# Sony_remote.net
KiCad netlist of a schematic drawn in EAGLE
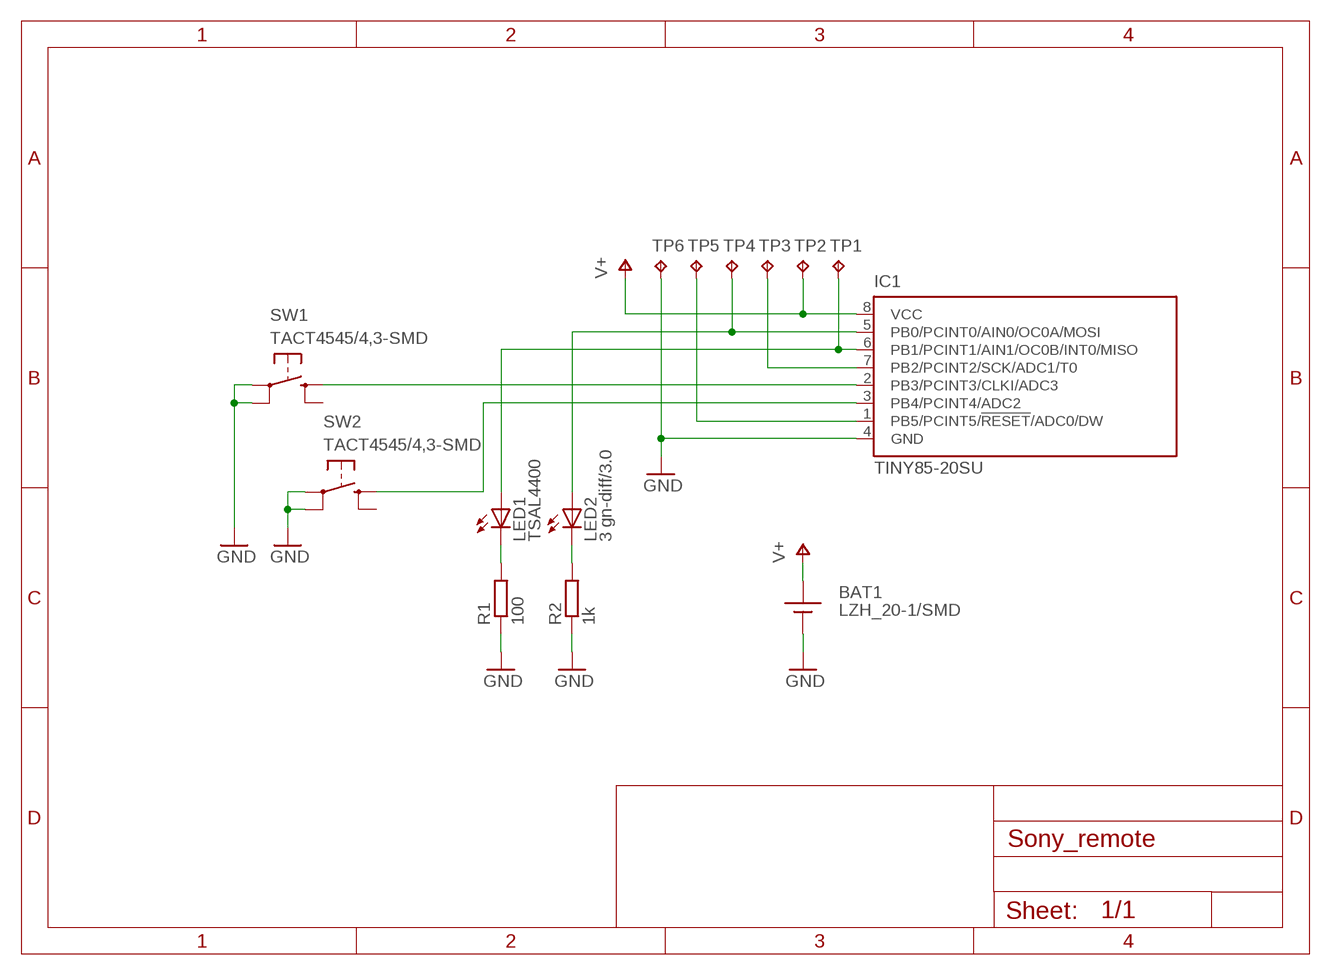
[diagram p0: schematic, sheet 1]

(export (version "E")
  (design (tool "Eeschema 10.0.6"))
  (components
    (comp (ref "BAT1")
      (value "LZH_20-1/SMD")
      (footprint "eagle-import:LZH_20-1_SMD")
      (libsource (lib "eagle-import") (part "LZH_20-1/SMD"))
    )
    (comp (ref "IC1")
      (value "TINY85-20SU")
      (footprint "eagle-import:8S2")
      (fields (field (name "MPN") "ATTINY13-20SU"))
      (libsource (lib "eagle-import") (part "TINY13SU-20"))
    )
    (comp (ref "LED1")
      (value "TSAL4400")
      (footprint "eagle-import:LED3MM")
      (libsource (lib "eagle-import") (part "LED3MM"))
    )
    (comp (ref "LED2")
      (value "3 gn-diff/3.0")
      (footprint "eagle-import:LED3MM")
      (libsource (lib "eagle-import") (part "LED3MM"))
    )
    (comp (ref "R1")
      (value "100")
      (footprint "eagle-import:M0805")
      (libsource (lib "eagle-import") (part "R-EU_M0805"))
    )
    (comp (ref "R2")
      (value "1k")
      (footprint "eagle-import:M0805")
      (libsource (lib "eagle-import") (part "R-EU_M0805"))
    )
    (comp (ref "SW1")
      (value "TACT4545/4,3-SMD")
      (footprint "eagle-import:TACT4545-SMD")
      (libsource (lib "eagle-import") (part "TACT4545-SMD"))
    )
    (comp (ref "SW2")
      (value "TACT4545/4,3-SMD")
      (footprint "eagle-import:TACT4545-SMD")
      (libsource (lib "eagle-import") (part "TACT4545-SMD"))
    )
    (comp (ref "TP1")
      (value "MISO")
      (footprint "eagle-import:B1,27")
      (libsource (lib "eagle-import") (part "TPB1,27"))
    )
    (comp (ref "TP2")
      (value "VCC")
      (footprint "eagle-import:B1,27")
      (libsource (lib "eagle-import") (part "TPB1,27"))
    )
    (comp (ref "TP3")
      (value "SCK")
      (footprint "eagle-import:B1,27")
      (libsource (lib "eagle-import") (part "TPB1,27"))
    )
    (comp (ref "TP4")
      (value "MOSI")
      (footprint "eagle-import:B1,27")
      (libsource (lib "eagle-import") (part "TPB1,27"))
    )
    (comp (ref "TP5")
      (value "RST")
      (footprint "eagle-import:B1,27")
      (libsource (lib "eagle-import") (part "TPB1,27"))
    )
    (comp (ref "TP6")
      (value "GND")
      (footprint "eagle-import:B1,27")
      (libsource (lib "eagle-import") (part "TPB1,27"))
    )
  )
  (nets
    (net (code "1") (name "GND") (class "Default")
      (node (ref "BAT1") (pin "-") (pinfunction "-_-") (pintype "bidirectional"))
      (node (ref "IC1") (pin "4") (pinfunction "GND_4") (pintype "power_in"))
      (node (ref "R1") (pin "1") (pinfunction "1_1") (pintype "passive"))
      (node (ref "R2") (pin "1") (pinfunction "1_1") (pintype "passive"))
      (node (ref "SW1") (pin "P$1") (pinfunction "P_P$1") (pintype "passive"))
      (node (ref "SW1") (pin "P$2") (pinfunction "P1_P$2") (pintype "passive"))
      (node (ref "SW2") (pin "P$1") (pinfunction "P_P$1") (pintype "passive"))
      (node (ref "SW2") (pin "P$2") (pinfunction "P1_P$2") (pintype "passive"))
      (node (ref "TP6") (pin "TP") (pinfunction "TP_TP") (pintype "input"))
    )
    (net (code "2") (name "Net-(IC1-PB0{slash}PCINT0{slash}AIN0{slash}OC0A{slash}MOSI)") (class "Default")
      (node (ref "IC1") (pin "5") (pinfunction "PB0/PCINT0/AIN0/OC0A/MOSI_5") (pintype "bidirectional"))
      (node (ref "LED2") (pin "A") (pinfunction "A_A") (pintype "passive"))
      (node (ref "TP4") (pin "TP") (pinfunction "TP_TP") (pintype "input"))
    )
    (net (code "3") (name "Net-(IC1-PB1{slash}PCINT1{slash}AIN1{slash}OC0B{slash}INT0{slash}MISO)") (class "Default")
      (node (ref "IC1") (pin "6") (pinfunction "PB1/PCINT1/AIN1/OC0B/INT0/MISO_6") (pintype "bidirectional"))
      (node (ref "LED1") (pin "A") (pinfunction "A_A") (pintype "passive"))
      (node (ref "TP1") (pin "TP") (pinfunction "TP_TP") (pintype "input"))
    )
    (net (code "4") (name "Net-(IC1-PB2{slash}PCINT2{slash}SCK{slash}ADC1{slash}T0)") (class "Default")
      (node (ref "IC1") (pin "7") (pinfunction "PB2/PCINT2/SCK/ADC1/T0_7") (pintype "bidirectional"))
      (node (ref "TP3") (pin "TP") (pinfunction "TP_TP") (pintype "input"))
    )
    (net (code "5") (name "Net-(IC1-PB3{slash}PCINT3{slash}CLKI{slash}ADC3)") (class "Default")
      (node (ref "IC1") (pin "2") (pinfunction "PB3/PCINT3/CLKI/ADC3_2") (pintype "bidirectional"))
      (node (ref "SW1") (pin "P$3") (pinfunction "S_P$3") (pintype "passive"))
    )
    (net (code "6") (name "Net-(IC1-PB4{slash}PCINT4{slash}ADC2)") (class "Default")
      (node (ref "IC1") (pin "3") (pinfunction "PB4/PCINT4/ADC2_3") (pintype "bidirectional"))
      (node (ref "SW2") (pin "P$3") (pinfunction "S_P$3") (pintype "passive"))
    )
    (net (code "7") (name "Net-(IC1-PB5{slash}PCINT5{slash}~{RESET}{slash}ADC0{slash}DW)") (class "Default")
      (node (ref "IC1") (pin "1") (pinfunction "PB5/PCINT5/~{RESET}/ADC0/DW_1") (pintype "bidirectional"))
      (node (ref "TP5") (pin "TP") (pinfunction "TP_TP") (pintype "input"))
    )
    (net (code "8") (name "Net-(LED1-C)") (class "Default")
      (node (ref "LED1") (pin "K") (pinfunction "C_K") (pintype "passive"))
      (node (ref "R1") (pin "2") (pinfunction "2_2") (pintype "passive"))
    )
    (net (code "9") (name "Net-(LED2-C)") (class "Default")
      (node (ref "LED2") (pin "K") (pinfunction "C_K") (pintype "passive"))
      (node (ref "R2") (pin "2") (pinfunction "2_2") (pintype "passive"))
    )
    (net (code "10") (name "V+") (class "Default")
      (node (ref "BAT1") (pin "+") (pinfunction "+_+") (pintype "bidirectional"))
      (node (ref "IC1") (pin "8") (pinfunction "VCC_8") (pintype "power_in"))
      (node (ref "TP2") (pin "TP") (pinfunction "TP_TP") (pintype "input"))
    )
    (net (code "11") (name "unconnected-(SW1-S1-PadP$4)") (class "Default")
      (node (ref "SW1") (pin "P$4") (pinfunction "S1_P$4") (pintype "passive"))
    )
    (net (code "12") (name "unconnected-(SW2-S1-PadP$4)") (class "Default")
      (node (ref "SW2") (pin "P$4") (pinfunction "S1_P$4") (pintype "passive"))
    )
  )
)
